# ltc_adaptor_v0.net
KiCad netlist of a schematic drawn in EAGLE
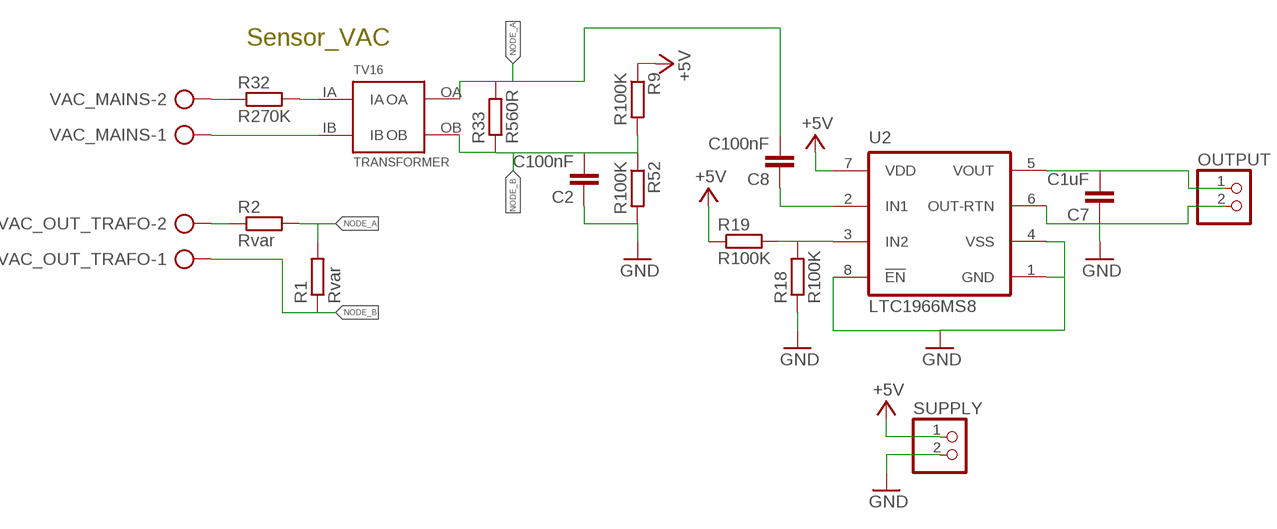
[diagram p0: schematic, sheet 1]

(export (version "E")
  (design (tool "Eeschema 10.0.6"))
  (components
    (comp (ref "C2")
      (value "C100nF")
      (footprint "eagle-import:C0805K")
      (libsource (lib "eagle-import") (part "C-EUC0805K"))
    )
    (comp (ref "C7")
      (value "C1uF")
      (footprint "eagle-import:C0805K")
      (libsource (lib "eagle-import") (part "C-EUC0805K"))
    )
    (comp (ref "C8")
      (value "C100nF")
      (footprint "eagle-import:C0805K")
      (libsource (lib "eagle-import") (part "C-EUC0805K"))
    )
    (comp (ref "OUTPUT")
      (value "HEADER-1X2ROUND")
      (footprint "eagle-import:1X02_ROUND")
      (libsource (lib "eagle-import") (part "HEADER-1X2ROUND"))
    )
    (comp (ref "R1")
      (value "Rvar")
      (footprint "eagle-import:R0805")
      (libsource (lib "eagle-import") (part "R-EU_R0805"))
    )
    (comp (ref "R2")
      (value "Rvar")
      (footprint "eagle-import:R0805")
      (libsource (lib "eagle-import") (part "R-EU_R0805"))
    )
    (comp (ref "R9")
      (value "R100K")
      (footprint "eagle-import:R0805")
      (libsource (lib "eagle-import") (part "R-EU_R0805"))
    )
    (comp (ref "R18")
      (value "R100K")
      (footprint "eagle-import:R0805")
      (libsource (lib "eagle-import") (part "R-EU_R0805"))
    )
    (comp (ref "R19")
      (value "R100K")
      (footprint "eagle-import:R0805")
      (libsource (lib "eagle-import") (part "R-EU_R0805"))
    )
    (comp (ref "R32")
      (value "R270K")
      (footprint "eagle-import:0309_10")
      (libsource (lib "eagle-import") (part "R-EU_0309/10"))
    )
    (comp (ref "R33")
      (value "R560R")
      (footprint "eagle-import:0309_10")
      (libsource (lib "eagle-import") (part "R-EU_0309/10"))
    )
    (comp (ref "R52")
      (value "R100K")
      (footprint "eagle-import:R0805")
      (libsource (lib "eagle-import") (part "R-EU_R0805"))
    )
    (comp (ref "SUPPLY")
      (value "HEADER-1X2ROUND")
      (footprint "eagle-import:1X02_ROUND")
      (libsource (lib "eagle-import") (part "HEADER-1X2ROUND"))
    )
    (comp (ref "TV16")
      (value "TRANSFORMER")
      (footprint "eagle-import:TV16")
      (libsource (lib "eagle-import") (part "TRANSFORMER"))
    )
    (comp (ref "U2")
      (value "LTC1966MS8")
      (footprint "eagle-import:MSOP08")
      (libsource (lib "eagle-import") (part "LTC1966MS8"))
    )
    (comp (ref "VAC_MAINS")
      (value "AK300/2")
      (footprint "eagle-import:AK300_2")
      (libsource (lib "eagle-import") (part "AK300/2"))
    )
    (comp (ref "VAC_OUT_TRAFO")
      (value "AK300/2")
      (footprint "eagle-import:AK300_2")
      (libsource (lib "eagle-import") (part "AK300/2"))
    )
  )
  (nets
    (net (code "1") (name "+5V") (class "Default")
      (node (ref "R19") (pin "1") (pinfunction "1_1") (pintype "passive"))
      (node (ref "R9") (pin "1") (pinfunction "1_1") (pintype "passive"))
      (node (ref "SUPPLY") (pin "1") (pinfunction "1_1") (pintype "passive"))
      (node (ref "U2") (pin "7") (pinfunction "VDD_7") (pintype "power_in"))
    )
    (net (code "2") (name "GND") (class "Default")
      (node (ref "C2") (pin "1") (pinfunction "1_1") (pintype "passive"))
      (node (ref "C7") (pin "1") (pinfunction "1_1") (pintype "passive"))
      (node (ref "OUTPUT") (pin "2") (pinfunction "2_2") (pintype "passive"))
      (node (ref "R18") (pin "1") (pinfunction "1_1") (pintype "passive"))
      (node (ref "R52") (pin "2") (pinfunction "2_2") (pintype "passive"))
      (node (ref "SUPPLY") (pin "2") (pinfunction "2_2") (pintype "passive"))
      (node (ref "U2") (pin "1") (pinfunction "GND_1") (pintype "power_in"))
      (node (ref "U2") (pin "4") (pinfunction "VSS_4") (pintype "power_in"))
      (node (ref "U2") (pin "6") (pinfunction "OUT-RTN_6") (pintype "passive"))
      (node (ref "U2") (pin "8") (pinfunction "~{EN}_8") (pintype "input"))
    )
    (net (code "3") (name "NODE_A") (class "Default")
      (node (ref "C8") (pin "2") (pinfunction "2_2") (pintype "passive"))
      (node (ref "R1") (pin "2") (pinfunction "2_2") (pintype "passive"))
      (node (ref "R2") (pin "2") (pinfunction "2_2") (pintype "passive"))
      (node (ref "R33") (pin "2") (pinfunction "2_2") (pintype "passive"))
      (node (ref "TV16") (pin "OA") (pinfunction "OA_OA") (pintype "bidirectional"))
    )
    (net (code "4") (name "NODE_B") (class "Default")
      (node (ref "C2") (pin "2") (pinfunction "2_2") (pintype "passive"))
      (node (ref "R1") (pin "1") (pinfunction "1_1") (pintype "passive"))
      (node (ref "R33") (pin "1") (pinfunction "1_1") (pintype "passive"))
      (node (ref "R52") (pin "1") (pinfunction "1_1") (pintype "passive"))
      (node (ref "R9") (pin "2") (pinfunction "2_2") (pintype "passive"))
      (node (ref "TV16") (pin "OB") (pinfunction "OB_OB") (pintype "bidirectional"))
      (node (ref "VAC_OUT_TRAFO") (pin "1") (pinfunction "KL_1") (pintype "passive"))
    )
    (net (code "5") (name "Net-(R32-Pad2)") (class "Default")
      (node (ref "R32") (pin "2") (pinfunction "2_2") (pintype "passive"))
      (node (ref "TV16") (pin "IA") (pinfunction "IA_IA") (pintype "bidirectional"))
    )
    (net (code "6") (name "Net-(U2-IN1)") (class "Default")
      (node (ref "C8") (pin "1") (pinfunction "1_1") (pintype "passive"))
      (node (ref "U2") (pin "2") (pinfunction "IN1_2") (pintype "input"))
    )
    (net (code "7") (name "Net-(U2-IN2)") (class "Default")
      (node (ref "R18") (pin "2") (pinfunction "2_2") (pintype "passive"))
      (node (ref "R19") (pin "2") (pinfunction "2_2") (pintype "passive"))
      (node (ref "U2") (pin "3") (pinfunction "IN2_3") (pintype "input"))
    )
    (net (code "8") (name "Net-(U2-VOUT)") (class "Default")
      (node (ref "C7") (pin "2") (pinfunction "2_2") (pintype "passive"))
      (node (ref "OUTPUT") (pin "1") (pinfunction "1_1") (pintype "passive"))
      (node (ref "U2") (pin "5") (pinfunction "VOUT_5") (pintype "output"))
    )
    (net (code "9") (name "Net-(VAC_MAINSA-KL)") (class "Default")
      (node (ref "TV16") (pin "IB") (pinfunction "IB_IB") (pintype "bidirectional"))
      (node (ref "VAC_MAINS") (pin "1") (pinfunction "KL_1") (pintype "passive"))
    )
    (net (code "10") (name "Net-(VAC_MAINSB-KL)") (class "Default")
      (node (ref "R32") (pin "1") (pinfunction "1_1") (pintype "passive"))
      (node (ref "VAC_MAINS") (pin "2") (pinfunction "KL_2") (pintype "passive"))
    )
    (net (code "11") (name "Net-(VAC_OUT_TRAFOB-KL)") (class "Default")
      (node (ref "R2") (pin "1") (pinfunction "1_1") (pintype "passive"))
      (node (ref "VAC_OUT_TRAFO") (pin "2") (pinfunction "KL_2") (pintype "passive"))
    )
  )
)
